# h-bridge2-smd-002.net
KiCad netlist of a schematic drawn in EAGLE
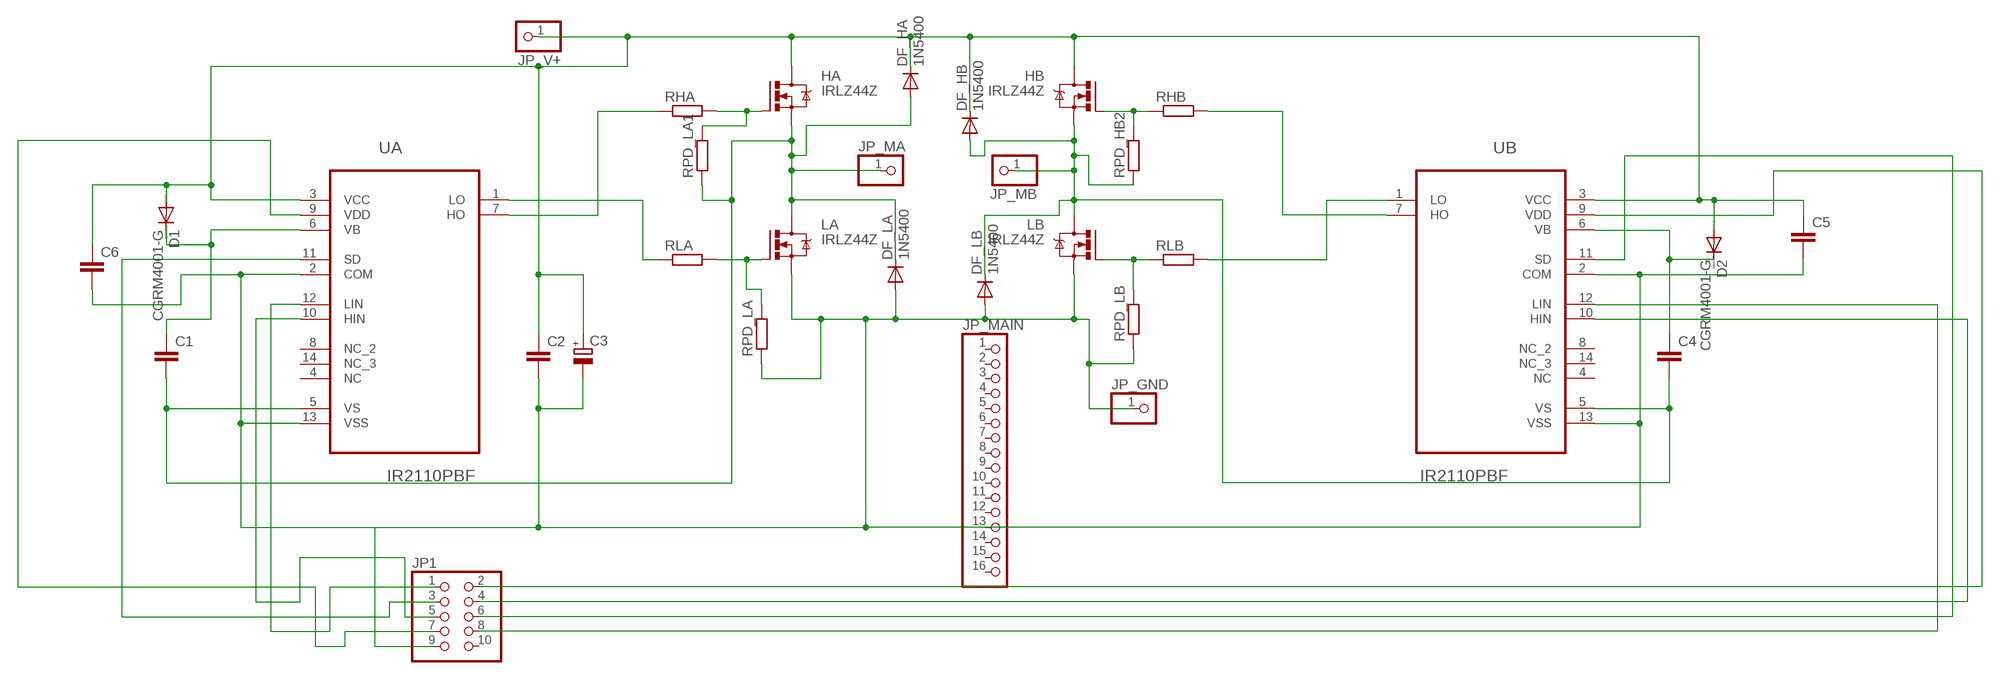
[diagram p0: schematic, sheet 1]

(export (version "E")
  (design (tool "Eeschema 10.0.6"))
  (components
    (comp (ref "C1")
      (value "C-EUC4532")
      (footprint "eagle-import:C4532")
      (libsource (lib "eagle-import") (part "C-EUC4532"))
    )
    (comp (ref "C2")
      (value "C-EU025-024X044")
      (footprint "eagle-import:C025-024X044")
      (libsource (lib "eagle-import") (part "C-EU025-024X044"))
    )
    (comp (ref "C3")
      (value "CPOL-EUE5-13")
      (footprint "eagle-import:E5-13")
      (libsource (lib "eagle-import") (part "CPOL-EUE5-13"))
    )
    (comp (ref "C4")
      (value "C-EUC4532")
      (footprint "eagle-import:C4532")
      (libsource (lib "eagle-import") (part "C-EUC4532"))
    )
    (comp (ref "C5")
      (value "C-EUC4532")
      (footprint "eagle-import:C4532")
      (libsource (lib "eagle-import") (part "C-EUC4532"))
    )
    (comp (ref "C6")
      (value "C-EUC4532")
      (footprint "eagle-import:C4532")
      (libsource (lib "eagle-import") (part "C-EUC4532"))
    )
    (comp (ref "D1")
      (value "CGRM4001-G")
      (footprint "eagle-import:SOD-123_MINI-SMA")
      (libsource (lib "eagle-import") (part "CGRM400-G1"))
    )
    (comp (ref "D2")
      (value "CGRM4001-G")
      (footprint "eagle-import:SOD-123_MINI-SMA")
      (libsource (lib "eagle-import") (part "CGRM400-G1"))
    )
    (comp (ref "DF_HA")
      (value "1N5400")
      (footprint "eagle-import:DO201-15")
      (libsource (lib "eagle-import") (part "1N5400"))
    )
    (comp (ref "DF_HB")
      (value "1N5400")
      (footprint "eagle-import:DO201-15")
      (libsource (lib "eagle-import") (part "1N5400"))
    )
    (comp (ref "DF_LA")
      (value "1N5400")
      (footprint "eagle-import:DO201-15")
      (libsource (lib "eagle-import") (part "1N5400"))
    )
    (comp (ref "DF_LB")
      (value "1N5400")
      (footprint "eagle-import:DO201-15")
      (libsource (lib "eagle-import") (part "1N5400"))
    )
    (comp (ref "HA")
      (value "IRLZ44Z")
      (footprint "eagle-import:TO220BH")
      (libsource (lib "eagle-import") (part "IRLZ44Z"))
    )
    (comp (ref "HB")
      (value "IRLZ44Z")
      (footprint "eagle-import:TO220BH")
      (libsource (lib "eagle-import") (part "IRLZ44Z"))
    )
    (comp (ref "JP1")
      (value "PINHD-2X5")
      (footprint "eagle-import:2X05")
      (libsource (lib "eagle-import") (part "PINHD-2X5"))
    )
    (comp (ref "JP_GND")
      (value "PINHD-1X1")
      (footprint "eagle-import:1X01")
      (libsource (lib "eagle-import") (part "PINHD-1X1"))
    )
    (comp (ref "JP_MA")
      (value "PINHD-1X1")
      (footprint "eagle-import:1X01")
      (libsource (lib "eagle-import") (part "PINHD-1X1"))
    )
    (comp (ref "JP_MAIN")
      (value "PINHD-1X16")
      (footprint "eagle-import:1X16")
      (libsource (lib "eagle-import") (part "PINHD-1X16"))
    )
    (comp (ref "JP_MB")
      (value "PINHD-1X1")
      (footprint "eagle-import:1X01")
      (libsource (lib "eagle-import") (part "PINHD-1X1"))
    )
    (comp (ref "JP_V+")
      (value "PINHD-1X1")
      (footprint "eagle-import:1X01")
      (libsource (lib "eagle-import") (part "PINHD-1X1"))
    )
    (comp (ref "LA")
      (value "IRLZ44Z")
      (footprint "eagle-import:TO220BH")
      (libsource (lib "eagle-import") (part "IRLZ44Z"))
    )
    (comp (ref "LB")
      (value "IRLZ44Z")
      (footprint "eagle-import:TO220BH")
      (libsource (lib "eagle-import") (part "IRLZ44Z"))
    )
    (comp (ref "RHA")
      (value "R-EU_R1206")
      (footprint "eagle-import:R1206")
      (libsource (lib "eagle-import") (part "R-EU_R1206"))
    )
    (comp (ref "RHB")
      (value "R-EU_R1206")
      (footprint "eagle-import:R1206")
      (libsource (lib "eagle-import") (part "R-EU_R1206"))
    )
    (comp (ref "RLA")
      (value "R-EU_R1206")
      (footprint "eagle-import:R1206")
      (libsource (lib "eagle-import") (part "R-EU_R1206"))
    )
    (comp (ref "RLB")
      (value "R-EU_R1206")
      (footprint "eagle-import:R1206")
      (libsource (lib "eagle-import") (part "R-EU_R1206"))
    )
    (comp (ref "RPD_HB2")
      (value "R-EU_R1206")
      (footprint "eagle-import:R1206")
      (libsource (lib "eagle-import") (part "R-EU_R1206"))
    )
    (comp (ref "RPD_LA")
      (value "R-EU_R1206")
      (footprint "eagle-import:R1206")
      (libsource (lib "eagle-import") (part "R-EU_R1206"))
    )
    (comp (ref "RPD_LA1")
      (value "R-EU_R1206")
      (footprint "eagle-import:R1206")
      (libsource (lib "eagle-import") (part "R-EU_R1206"))
    )
    (comp (ref "RPD_LB")
      (value "R-EU_R1206")
      (footprint "eagle-import:R1206")
      (libsource (lib "eagle-import") (part "R-EU_R1206"))
    )
    (comp (ref "UA")
      (value "IR2110PBF")
      (footprint "eagle-import:DIP254P762X533-14")
      (libsource (lib "eagle-import") (part "IR2110PBF"))
    )
    (comp (ref "UB")
      (value "IR2110PBF")
      (footprint "eagle-import:DIP254P762X533-14")
      (libsource (lib "eagle-import") (part "IR2110PBF"))
    )
  )
  (nets
    (net (code "1") (name "Net-(HA-PadG)") (class "Default")
      (node (ref "HA") (pin "G") (pinfunction "G_G") (pintype "passive"))
      (node (ref "RHA") (pin "2") (pinfunction "2_2") (pintype "passive"))
      (node (ref "RPD_LA1") (pin "2") (pinfunction "2_2") (pintype "passive"))
    )
    (net (code "2") (name "Net-(HB-PadG)") (class "Default")
      (node (ref "HB") (pin "G") (pinfunction "G_G") (pintype "passive"))
      (node (ref "RHB") (pin "1") (pinfunction "1_1") (pintype "passive"))
      (node (ref "RPD_HB2") (pin "2") (pinfunction "2_2") (pintype "passive"))
    )
    (net (code "3") (name "Net-(LA-PadG)") (class "Default")
      (node (ref "LA") (pin "G") (pinfunction "G_G") (pintype "passive"))
      (node (ref "RLA") (pin "2") (pinfunction "2_2") (pintype "passive"))
      (node (ref "RPD_LA") (pin "2") (pinfunction "2_2") (pintype "passive"))
    )
    (net (code "4") (name "Net-(LB-PadG)") (class "Default")
      (node (ref "LB") (pin "G") (pinfunction "G_G") (pintype "passive"))
      (node (ref "RLB") (pin "1") (pinfunction "1_1") (pintype "passive"))
      (node (ref "RPD_LB") (pin "2") (pinfunction "2_2") (pintype "passive"))
    )
    (net (code "5") (name "Net-(UA-COM)") (class "Default")
      (node (ref "C2") (pin "2") (pinfunction "2_2") (pintype "passive"))
      (node (ref "C3") (pin "-") (pinfunction "-_-") (pintype "passive"))
      (node (ref "C5") (pin "2") (pinfunction "2_2") (pintype "passive"))
      (node (ref "C6") (pin "2") (pinfunction "2_2") (pintype "passive"))
      (node (ref "DF_LA") (pin "A") (pinfunction "A_A") (pintype "passive"))
      (node (ref "DF_LB") (pin "A") (pinfunction "A_A") (pintype "passive"))
      (node (ref "JP1") (pin "9") (pinfunction "9_9") (pintype "passive"))
      (node (ref "JP_GND") (pin "1") (pinfunction "1_1") (pintype "passive"))
      (node (ref "LA") (pin "S") (pinfunction "S_S") (pintype "passive"))
      (node (ref "LB") (pin "S") (pinfunction "S_S") (pintype "passive"))
      (node (ref "RPD_LA") (pin "1") (pinfunction "1_1") (pintype "passive"))
      (node (ref "RPD_LB") (pin "1") (pinfunction "1_1") (pintype "passive"))
      (node (ref "UA") (pin "13") (pinfunction "VSS_13") (pintype "power_in"))
      (node (ref "UA") (pin "2") (pinfunction "COM_2") (pintype "passive"))
      (node (ref "UB") (pin "13") (pinfunction "VSS_13") (pintype "power_in"))
      (node (ref "UB") (pin "2") (pinfunction "COM_2") (pintype "passive"))
    )
    (net (code "6") (name "Net-(UA-HIN)") (class "Default")
      (node (ref "JP1") (pin "5") (pinfunction "5_5") (pintype "passive"))
      (node (ref "UA") (pin "10") (pinfunction "HIN_10") (pintype "input"))
    )
    (net (code "7") (name "Net-(UA-HO)") (class "Default")
      (node (ref "RHA") (pin "1") (pinfunction "1_1") (pintype "passive"))
      (node (ref "UA") (pin "7") (pinfunction "HO_7") (pintype "output"))
    )
    (net (code "8") (name "Net-(UA-LIN)") (class "Default")
      (node (ref "JP1") (pin "1") (pinfunction "1_1") (pintype "passive"))
      (node (ref "UA") (pin "12") (pinfunction "LIN_12") (pintype "input"))
    )
    (net (code "9") (name "Net-(UA-LO)") (class "Default")
      (node (ref "RLA") (pin "1") (pinfunction "1_1") (pintype "passive"))
      (node (ref "UA") (pin "1") (pinfunction "LO_1") (pintype "output"))
    )
    (net (code "10") (name "Net-(UA-SD)") (class "Default")
      (node (ref "JP1") (pin "3") (pinfunction "3_3") (pintype "passive"))
      (node (ref "UA") (pin "11") (pinfunction "SD_11") (pintype "input"))
    )
    (net (code "11") (name "Net-(UA-VB)") (class "Default")
      (node (ref "C1") (pin "1") (pinfunction "1_1") (pintype "passive"))
      (node (ref "D1") (pin "C") (pinfunction "C_C") (pintype "passive"))
      (node (ref "UA") (pin "6") (pinfunction "VB_6") (pintype "power_in"))
    )
    (net (code "12") (name "Net-(UA-VCC)") (class "Default")
      (node (ref "C2") (pin "1") (pinfunction "1_1") (pintype "passive"))
      (node (ref "C3") (pin "+") (pinfunction "+_+") (pintype "passive"))
      (node (ref "C5") (pin "1") (pinfunction "1_1") (pintype "passive"))
      (node (ref "C6") (pin "1") (pinfunction "1_1") (pintype "passive"))
      (node (ref "D1") (pin "A") (pinfunction "A_A") (pintype "passive"))
      (node (ref "D2") (pin "A") (pinfunction "A_A") (pintype "passive"))
      (node (ref "DF_HA") (pin "C") (pinfunction "C_C") (pintype "passive"))
      (node (ref "DF_HB") (pin "C") (pinfunction "C_C") (pintype "passive"))
      (node (ref "HA") (pin "D") (pinfunction "D_D") (pintype "passive"))
      (node (ref "HB") (pin "D") (pinfunction "D_D") (pintype "passive"))
      (node (ref "JP_V+") (pin "1") (pinfunction "1_1") (pintype "passive"))
      (node (ref "UA") (pin "3") (pinfunction "VCC_3") (pintype "power_in"))
      (node (ref "UB") (pin "3") (pinfunction "VCC_3") (pintype "power_in"))
    )
    (net (code "13") (name "Net-(UA-VDD)") (class "Default")
      (node (ref "JP1") (pin "7") (pinfunction "7_7") (pintype "passive"))
      (node (ref "UA") (pin "9") (pinfunction "VDD_9") (pintype "power_in"))
    )
    (net (code "14") (name "Net-(UA-VS)") (class "Default")
      (node (ref "C1") (pin "2") (pinfunction "2_2") (pintype "passive"))
      (node (ref "DF_HA") (pin "A") (pinfunction "A_A") (pintype "passive"))
      (node (ref "DF_LA") (pin "C") (pinfunction "C_C") (pintype "passive"))
      (node (ref "HA") (pin "S") (pinfunction "S_S") (pintype "passive"))
      (node (ref "JP_MA") (pin "1") (pinfunction "1_1") (pintype "passive"))
      (node (ref "LA") (pin "D") (pinfunction "D_D") (pintype "passive"))
      (node (ref "RPD_LA1") (pin "1") (pinfunction "1_1") (pintype "passive"))
      (node (ref "UA") (pin "5") (pinfunction "VS_5") (pintype "power_in"))
    )
    (net (code "15") (name "Net-(UB-HIN)") (class "Default")
      (node (ref "JP1") (pin "4") (pinfunction "4_4") (pintype "passive"))
      (node (ref "UB") (pin "10") (pinfunction "HIN_10") (pintype "input"))
    )
    (net (code "16") (name "Net-(UB-HO)") (class "Default")
      (node (ref "RHB") (pin "2") (pinfunction "2_2") (pintype "passive"))
      (node (ref "UB") (pin "7") (pinfunction "HO_7") (pintype "output"))
    )
    (net (code "17") (name "Net-(UB-LIN)") (class "Default")
      (node (ref "JP1") (pin "8") (pinfunction "8_8") (pintype "passive"))
      (node (ref "UB") (pin "12") (pinfunction "LIN_12") (pintype "input"))
    )
    (net (code "18") (name "Net-(UB-LO)") (class "Default")
      (node (ref "RLB") (pin "2") (pinfunction "2_2") (pintype "passive"))
      (node (ref "UB") (pin "1") (pinfunction "LO_1") (pintype "output"))
    )
    (net (code "19") (name "Net-(UB-SD)") (class "Default")
      (node (ref "JP1") (pin "6") (pinfunction "6_6") (pintype "passive"))
      (node (ref "UB") (pin "11") (pinfunction "SD_11") (pintype "input"))
    )
    (net (code "20") (name "Net-(UB-VB)") (class "Default")
      (node (ref "C4") (pin "1") (pinfunction "1_1") (pintype "passive"))
      (node (ref "D2") (pin "C") (pinfunction "C_C") (pintype "passive"))
      (node (ref "UB") (pin "6") (pinfunction "VB_6") (pintype "power_in"))
    )
    (net (code "21") (name "Net-(UB-VDD)") (class "Default")
      (node (ref "JP1") (pin "2") (pinfunction "2_2") (pintype "passive"))
      (node (ref "UB") (pin "9") (pinfunction "VDD_9") (pintype "power_in"))
    )
    (net (code "22") (name "Net-(UB-VS)") (class "Default")
      (node (ref "C4") (pin "2") (pinfunction "2_2") (pintype "passive"))
      (node (ref "DF_HB") (pin "A") (pinfunction "A_A") (pintype "passive"))
      (node (ref "DF_LB") (pin "C") (pinfunction "C_C") (pintype "passive"))
      (node (ref "HB") (pin "S") (pinfunction "S_S") (pintype "passive"))
      (node (ref "JP_MB") (pin "1") (pinfunction "1_1") (pintype "passive"))
      (node (ref "LB") (pin "D") (pinfunction "D_D") (pintype "passive"))
      (node (ref "RPD_HB2") (pin "1") (pinfunction "1_1") (pintype "passive"))
      (node (ref "UB") (pin "5") (pinfunction "VS_5") (pintype "power_in"))
    )
    (net (code "23") (name "unconnected-(JP1-Pad10)") (class "Default")
      (node (ref "JP1") (pin "10") (pinfunction "10_10") (pintype "passive"))
    )
    (net (code "24") (name "unconnected-(JP_MAIN-Pad1)") (class "Default")
      (node (ref "JP_MAIN") (pin "1") (pinfunction "1_1") (pintype "passive"))
    )
    (net (code "25") (name "unconnected-(JP_MAIN-Pad2)") (class "Default")
      (node (ref "JP_MAIN") (pin "2") (pinfunction "2_2") (pintype "passive"))
    )
    (net (code "26") (name "unconnected-(JP_MAIN-Pad3)") (class "Default")
      (node (ref "JP_MAIN") (pin "3") (pinfunction "3_3") (pintype "passive"))
    )
    (net (code "27") (name "unconnected-(JP_MAIN-Pad4)") (class "Default")
      (node (ref "JP_MAIN") (pin "4") (pinfunction "4_4") (pintype "passive"))
    )
    (net (code "28") (name "unconnected-(JP_MAIN-Pad5)") (class "Default")
      (node (ref "JP_MAIN") (pin "5") (pinfunction "5_5") (pintype "passive"))
    )
    (net (code "29") (name "unconnected-(JP_MAIN-Pad6)") (class "Default")
      (node (ref "JP_MAIN") (pin "6") (pinfunction "6_6") (pintype "passive"))
    )
    (net (code "30") (name "unconnected-(JP_MAIN-Pad7)") (class "Default")
      (node (ref "JP_MAIN") (pin "7") (pinfunction "7_7") (pintype "passive"))
    )
    (net (code "31") (name "unconnected-(JP_MAIN-Pad8)") (class "Default")
      (node (ref "JP_MAIN") (pin "8") (pinfunction "8_8") (pintype "passive"))
    )
    (net (code "32") (name "unconnected-(JP_MAIN-Pad9)") (class "Default")
      (node (ref "JP_MAIN") (pin "9") (pinfunction "9_9") (pintype "passive"))
    )
    (net (code "33") (name "unconnected-(JP_MAIN-Pad10)") (class "Default")
      (node (ref "JP_MAIN") (pin "10") (pinfunction "10_10") (pintype "passive"))
    )
    (net (code "34") (name "unconnected-(JP_MAIN-Pad11)") (class "Default")
      (node (ref "JP_MAIN") (pin "11") (pinfunction "11_11") (pintype "passive"))
    )
    (net (code "35") (name "unconnected-(JP_MAIN-Pad12)") (class "Default")
      (node (ref "JP_MAIN") (pin "12") (pinfunction "12_12") (pintype "passive"))
    )
    (net (code "36") (name "unconnected-(JP_MAIN-Pad13)") (class "Default")
      (node (ref "JP_MAIN") (pin "13") (pinfunction "13_13") (pintype "passive"))
    )
    (net (code "37") (name "unconnected-(JP_MAIN-Pad14)") (class "Default")
      (node (ref "JP_MAIN") (pin "14") (pinfunction "14_14") (pintype "passive"))
    )
    (net (code "38") (name "unconnected-(JP_MAIN-Pad15)") (class "Default")
      (node (ref "JP_MAIN") (pin "15") (pinfunction "15_15") (pintype "passive"))
    )
    (net (code "39") (name "unconnected-(JP_MAIN-Pad16)") (class "Default")
      (node (ref "JP_MAIN") (pin "16") (pinfunction "16_16") (pintype "passive"))
    )
    (net (code "40") (name "unconnected-(UA-NC-Pad4)") (class "Default")
      (node (ref "UA") (pin "4") (pinfunction "NC_4") (pintype "no_connect"))
    )
    (net (code "41") (name "unconnected-(UA-NC_2-Pad8)") (class "Default")
      (node (ref "UA") (pin "8") (pinfunction "NC_2_8") (pintype "no_connect"))
    )
    (net (code "42") (name "unconnected-(UA-NC_3-Pad14)") (class "Default")
      (node (ref "UA") (pin "14") (pinfunction "NC_3_14") (pintype "no_connect"))
    )
    (net (code "43") (name "unconnected-(UB-NC-Pad4)") (class "Default")
      (node (ref "UB") (pin "4") (pinfunction "NC_4") (pintype "no_connect"))
    )
    (net (code "44") (name "unconnected-(UB-NC_2-Pad8)") (class "Default")
      (node (ref "UB") (pin "8") (pinfunction "NC_2_8") (pintype "no_connect"))
    )
    (net (code "45") (name "unconnected-(UB-NC_3-Pad14)") (class "Default")
      (node (ref "UB") (pin "14") (pinfunction "NC_3_14") (pintype "no_connect"))
    )
  )
)
